# Axis_Channel.net
KiCad netlist of a schematic drawn in Altium Designer
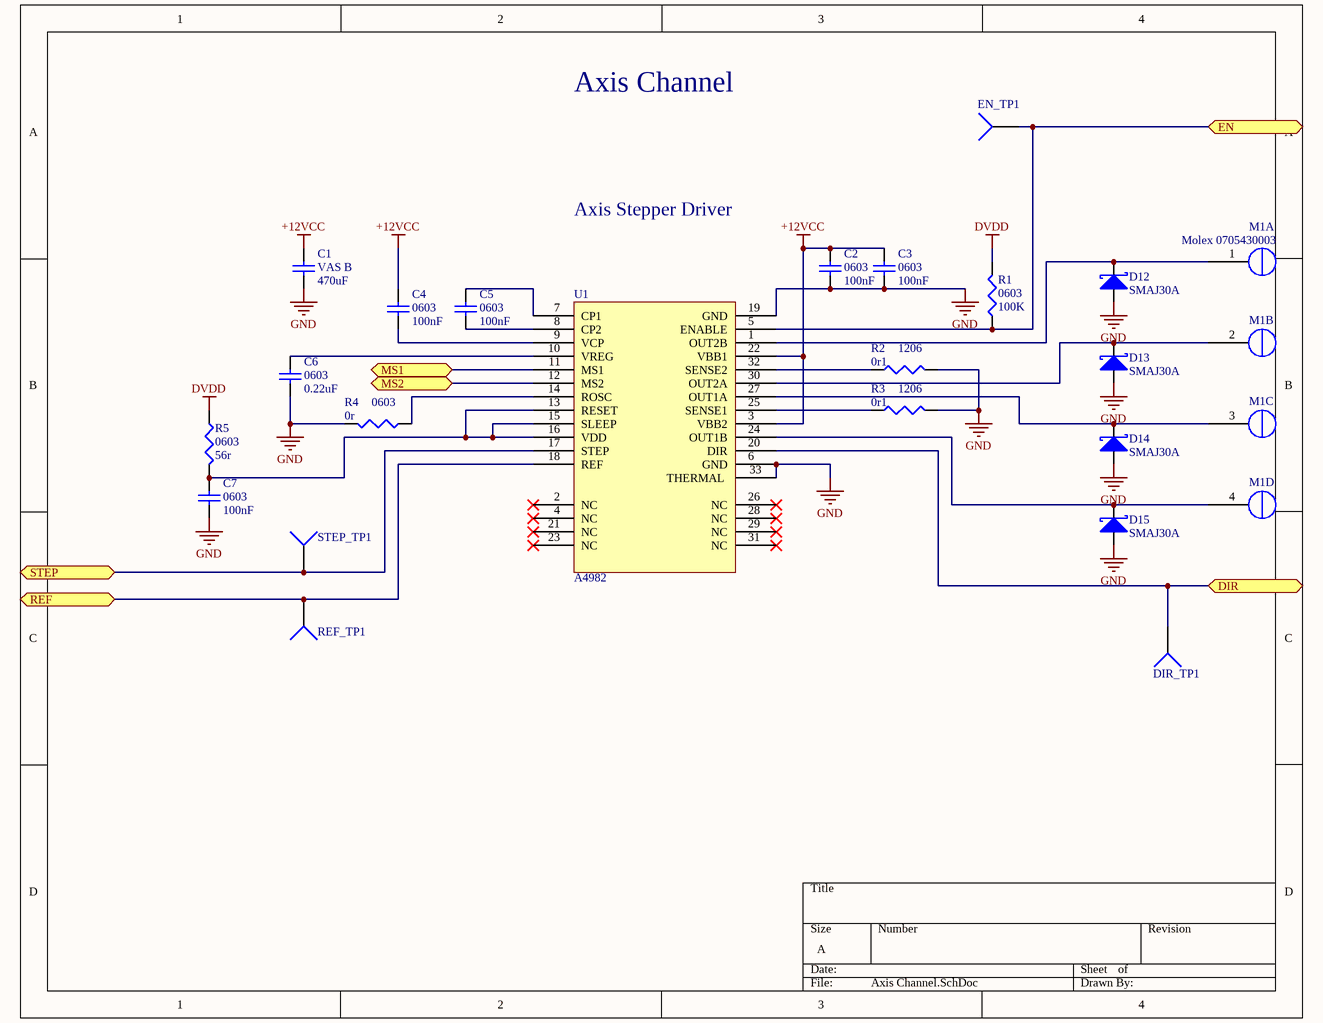
[diagram p0: Axis Channel.SchDoc]

(export (version "E")
  (design (tool "Eeschema 10.0.6"))
  (components
    (comp (ref "C1")
      (value "VAS B")
      (footprint "Panasonic VS B")
      (description "Capacitor (Semiconductor SIM Model)")
      (fields (field (name "ALTIUM_VALUE") "470uF") (field (name "PUBLISHER") "Altium Limited"))
      (libsource (lib "Miscellaneous Devices") (part "Cap Semi"))
    )
    (comp (ref "C2")
      (value "0603")
      (footprint "1608[0603]")
      (description "Capacitor (Semiconductor SIM Model)")
      (fields (field (name "ALTIUM_VALUE") "100nF") (field (name "PUBLISHER") "Altium Limited"))
      (libsource (lib "Miscellaneous Devices") (part "Cap Semi"))
    )
    (comp (ref "C3")
      (value "0603")
      (footprint "1608[0603]")
      (description "Capacitor (Semiconductor SIM Model)")
      (fields (field (name "ALTIUM_VALUE") "100nF") (field (name "PUBLISHER") "Altium Limited"))
      (libsource (lib "Miscellaneous Devices") (part "Cap Semi"))
    )
    (comp (ref "C4")
      (value "0603")
      (footprint "1608[0603]")
      (description "Capacitor (Semiconductor SIM Model)")
      (fields (field (name "ALTIUM_VALUE") "100nF") (field (name "PUBLISHER") "Altium Limited"))
      (libsource (lib "Miscellaneous Devices") (part "Cap Semi"))
    )
    (comp (ref "C5")
      (value "0603")
      (footprint "1608[0603]")
      (description "Capacitor (Semiconductor SIM Model)")
      (fields (field (name "ALTIUM_VALUE") "100nF") (field (name "PUBLISHER") "Altium Limited"))
      (libsource (lib "Miscellaneous Devices") (part "Cap Semi"))
    )
    (comp (ref "C6")
      (value "0603")
      (footprint "1608[0603]")
      (description "Capacitor (Semiconductor SIM Model)")
      (fields (field (name "ALTIUM_VALUE") "0.22uF") (field (name "PUBLISHER") "Altium Limited"))
      (libsource (lib "Miscellaneous Devices") (part "Cap Semi"))
    )
    (comp (ref "C7")
      (value "0603")
      (footprint "1608[0603]")
      (description "Capacitor (Semiconductor SIM Model)")
      (fields (field (name "ALTIUM_VALUE") "100nF") (field (name "PUBLISHER") "Altium Limited"))
      (libsource (lib "Miscellaneous Devices") (part "Cap Semi"))
    )
    (comp (ref "D12")
      (value "SMAJ30A")
      (footprint "SMAJ30A")
      (fields (field (name "PUBLISHER") "Altium Limited"))
      (libsource (lib "ZMBo Schematic Library") (part "D SMAJ30A"))
    )
    (comp (ref "D13")
      (value "SMAJ30A")
      (footprint "SMAJ30A")
      (fields (field (name "PUBLISHER") "Altium Limited"))
      (libsource (lib "ZMBo Schematic Library") (part "D SMAJ30A"))
    )
    (comp (ref "D14")
      (value "SMAJ30A")
      (footprint "SMAJ30A")
      (fields (field (name "PUBLISHER") "Altium Limited"))
      (libsource (lib "ZMBo Schematic Library") (part "D SMAJ30A"))
    )
    (comp (ref "D15")
      (value "SMAJ30A")
      (footprint "SMAJ30A")
      (fields (field (name "PUBLISHER") "Altium Limited"))
      (libsource (lib "ZMBo Schematic Library") (part "D SMAJ30A"))
    )
    (comp (ref "DIR_TP1")
      (value "TP4")
      (footprint "PIN1")
      (description "Socket")
      (fields (field (name "PUBLISHER") "Altium Limited"))
      (libsource (lib "Miscellaneous Connectors") (part "Socket"))
    )
    (comp (ref "EN_TP1")
      (value "TP4")
      (footprint "PIN1")
      (description "Socket")
      (fields (field (name "PUBLISHER") "Altium Limited"))
      (libsource (lib "Miscellaneous Connectors") (part "Socket"))
    )
    (comp (ref "M1")
      (value "Molex 0705430003")
      (footprint "Molex 0705430003")
      (description "Molex 4 Pin Clip Connector")
      (libsource (lib "ZMBo Schematic Library") (part "Molex 0705430003 Alt"))
    )
    (comp (ref "R1")
      (value "0603")
      (footprint "J1-0603")
      (description "Resistor")
      (fields (field (name "ALTIUM_VALUE") "100K") (field (name "PUBLISHER") "Altium Limited"))
      (libsource (lib "Miscellaneous Devices") (part "Res3"))
    )
    (comp (ref "R2")
      (value "1206")
      (footprint "1206 SMD Resistor")
      (description "Resistor")
      (fields (field (name "ALTIUM_VALUE") "0r1") (field (name "PUBLISHER") "Altium Limited"))
      (libsource (lib "Miscellaneous Devices") (part "Res3"))
    )
    (comp (ref "R3")
      (value "1206")
      (footprint "1206 SMD Resistor")
      (description "Resistor")
      (fields (field (name "ALTIUM_VALUE") "0r1") (field (name "PUBLISHER") "Altium Limited"))
      (libsource (lib "Miscellaneous Devices") (part "Res3"))
    )
    (comp (ref "R4")
      (value "0603")
      (footprint "J1-0603")
      (description "Resistor")
      (fields (field (name "ALTIUM_VALUE") "0r") (field (name "PUBLISHER") "Altium Limited"))
      (libsource (lib "Miscellaneous Devices") (part "Res3"))
    )
    (comp (ref "R5")
      (value "0603")
      (footprint "J1-0603")
      (description "Resistor")
      (fields (field (name "ALTIUM_VALUE") "56r") (field (name "PUBLISHER") "Altium Limited"))
      (libsource (lib "Miscellaneous Devices") (part "Res3"))
    )
    (comp (ref "REF_TP1")
      (value "TP4")
      (footprint "PIN1")
      (description "Socket")
      (fields (field (name "PUBLISHER") "Altium Limited"))
      (libsource (lib "Miscellaneous Connectors") (part "Socket"))
    )
    (comp (ref "STEP_TP1")
      (value "TP4")
      (footprint "PIN1")
      (description "Socket")
      (fields (field (name "PUBLISHER") "Altium Limited"))
      (libsource (lib "Miscellaneous Connectors") (part "Socket"))
    )
    (comp (ref "U1")
      (value "A4982")
      (footprint "QFN50P508X508X100_HS-33N")
      (description "Alllegor A4982 Stepper Driver")
      (libsource (lib "RADMBo Schematic Library") (part "A4982"))
    )
  )
  (nets
    (net (code "1") (name "+12VCC") (class "Default")
      (node (ref "C1") (pin "2") (pinfunction "2_2") (pintype "passive"))
      (node (ref "C2") (pin "2") (pinfunction "2_2") (pintype "passive"))
      (node (ref "C3") (pin "2") (pinfunction "2_2") (pintype "passive"))
      (node (ref "C4") (pin "2") (pinfunction "2_2") (pintype "passive"))
      (node (ref "U1") (pin "22") (pinfunction "VBB1_22") (pintype "passive"))
      (node (ref "U1") (pin "3") (pinfunction "VBB2_3") (pintype "passive"))
    )
    (net (code "2") (name "/DIR") (class "Default")
      (node (ref "DIR_TP1") (pin "1") (pinfunction "1_1") (pintype "passive"))
      (node (ref "U1") (pin "20") (pinfunction "DIR_20") (pintype "passive"))
    )
    (net (code "3") (name "/EN") (class "Default")
      (node (ref "EN_TP1") (pin "1") (pinfunction "1_1") (pintype "passive"))
      (node (ref "R1") (pin "1") (pinfunction "1_1") (pintype "passive"))
      (node (ref "U1") (pin "5") (pinfunction "ENABLE_5") (pintype "passive"))
    )
    (net (code "4") (name "/MS1") (class "Default")
      (node (ref "U1") (pin "11") (pinfunction "MS1_11") (pintype "passive"))
    )
    (net (code "5") (name "/MS2") (class "Default")
      (node (ref "U1") (pin "12") (pinfunction "MS2_12") (pintype "passive"))
    )
    (net (code "6") (name "/REF") (class "Default")
      (node (ref "REF_TP1") (pin "1") (pinfunction "1_1") (pintype "passive"))
      (node (ref "U1") (pin "18") (pinfunction "REF_18") (pintype "passive"))
    )
    (net (code "7") (name "/STEP") (class "Default")
      (node (ref "STEP_TP1") (pin "1") (pinfunction "1_1") (pintype "passive"))
      (node (ref "U1") (pin "17") (pinfunction "STEP_17") (pintype "passive"))
    )
    (net (code "8") (name "DVDD") (class "Default")
      (node (ref "R1") (pin "2") (pinfunction "2_2") (pintype "passive"))
      (node (ref "R5") (pin "1") (pinfunction "1_1") (pintype "passive"))
    )
    (net (code "9") (name "GND") (class "Default")
      (node (ref "C1") (pin "1") (pinfunction "1_1") (pintype "passive"))
      (node (ref "C2") (pin "1") (pinfunction "1_1") (pintype "passive"))
      (node (ref "C3") (pin "1") (pinfunction "1_1") (pintype "passive"))
      (node (ref "C6") (pin "1") (pinfunction "1_1") (pintype "passive"))
      (node (ref "C7") (pin "1") (pinfunction "1_1") (pintype "passive"))
      (node (ref "D12") (pin "1") (pinfunction "A_1") (pintype "passive"))
      (node (ref "D13") (pin "1") (pinfunction "A_1") (pintype "passive"))
      (node (ref "D14") (pin "1") (pinfunction "A_1") (pintype "passive"))
      (node (ref "D15") (pin "1") (pinfunction "A_1") (pintype "passive"))
      (node (ref "R2") (pin "2") (pinfunction "2_2") (pintype "passive"))
      (node (ref "R3") (pin "2") (pinfunction "2_2") (pintype "passive"))
      (node (ref "R4") (pin "2") (pinfunction "2_2") (pintype "passive"))
      (node (ref "U1") (pin "19") (pinfunction "GND_19") (pintype "passive"))
      (node (ref "U1") (pin "33") (pinfunction "THERMAL_33") (pintype "passive"))
      (node (ref "U1") (pin "6") (pinfunction "GND_6") (pintype "passive"))
    )
    (net (code "10") (name "Net-(D12-K)") (class "Default")
      (node (ref "D12") (pin "2") (pinfunction "K_2") (pintype "passive"))
      (node (ref "M1") (pin "1") (pinfunction "OUT2B_1") (pintype "passive"))
      (node (ref "U1") (pin "1") (pinfunction "OUT2B_1") (pintype "passive"))
    )
    (net (code "11") (name "Net-(D13-K)") (class "Default")
      (node (ref "D13") (pin "2") (pinfunction "K_2") (pintype "passive"))
      (node (ref "M1") (pin "2") (pinfunction "OUT2A_2") (pintype "passive"))
      (node (ref "U1") (pin "30") (pinfunction "OUT2A_30") (pintype "passive"))
    )
    (net (code "12") (name "Net-(D14-K)") (class "Default")
      (node (ref "D14") (pin "2") (pinfunction "K_2") (pintype "passive"))
      (node (ref "M1") (pin "3") (pinfunction "OUT1A_3") (pintype "passive"))
      (node (ref "U1") (pin "27") (pinfunction "OUT1A_27") (pintype "passive"))
    )
    (net (code "13") (name "Net-(D15-K)") (class "Default")
      (node (ref "D15") (pin "2") (pinfunction "K_2") (pintype "passive"))
      (node (ref "M1") (pin "4") (pinfunction "OUT1B_4") (pintype "passive"))
      (node (ref "U1") (pin "24") (pinfunction "OUT1B_24") (pintype "passive"))
    )
    (net (code "14") (name "Net-(U1-CP1)") (class "Default")
      (node (ref "C5") (pin "2") (pinfunction "2_2") (pintype "passive"))
      (node (ref "U1") (pin "7") (pinfunction "CP1_7") (pintype "passive"))
    )
    (net (code "15") (name "Net-(U1-CP2)") (class "Default")
      (node (ref "C5") (pin "1") (pinfunction "1_1") (pintype "passive"))
      (node (ref "U1") (pin "8") (pinfunction "CP2_8") (pintype "passive"))
    )
    (net (code "16") (name "Net-(U1-RESET)") (class "Default")
      (node (ref "C7") (pin "2") (pinfunction "2_2") (pintype "passive"))
      (node (ref "R5") (pin "2") (pinfunction "2_2") (pintype "passive"))
      (node (ref "U1") (pin "13") (pinfunction "RESET_13") (pintype "passive"))
      (node (ref "U1") (pin "15") (pinfunction "SLEEP_15") (pintype "passive"))
      (node (ref "U1") (pin "16") (pinfunction "VDD_16") (pintype "passive"))
    )
    (net (code "17") (name "Net-(U1-ROSC)") (class "Default")
      (node (ref "R4") (pin "1") (pinfunction "1_1") (pintype "passive"))
      (node (ref "U1") (pin "14") (pinfunction "ROSC_14") (pintype "passive"))
    )
    (net (code "18") (name "Net-(U1-SENSE1)") (class "Default")
      (node (ref "R3") (pin "1") (pinfunction "1_1") (pintype "passive"))
      (node (ref "U1") (pin "25") (pinfunction "SENSE1_25") (pintype "passive"))
    )
    (net (code "19") (name "Net-(U1-SENSE2)") (class "Default")
      (node (ref "R2") (pin "1") (pinfunction "1_1") (pintype "passive"))
      (node (ref "U1") (pin "32") (pinfunction "SENSE2_32") (pintype "passive"))
    )
    (net (code "20") (name "Net-(U1-VCP)") (class "Default")
      (node (ref "C4") (pin "1") (pinfunction "1_1") (pintype "passive"))
      (node (ref "U1") (pin "9") (pinfunction "VCP_9") (pintype "passive"))
    )
    (net (code "21") (name "Net-(U1-VREG)") (class "Default")
      (node (ref "C6") (pin "2") (pinfunction "2_2") (pintype "passive"))
      (node (ref "U1") (pin "10") (pinfunction "VREG_10") (pintype "passive"))
    )
    (net (code "22") (name "unconnected-(U1-NC-Pad2)") (class "Default")
      (node (ref "U1") (pin "2") (pinfunction "NC_2") (pintype "passive+no_connect"))
    )
    (net (code "23") (name "unconnected-(U1-NC-Pad4)") (class "Default")
      (node (ref "U1") (pin "4") (pinfunction "NC_4") (pintype "passive+no_connect"))
    )
    (net (code "24") (name "unconnected-(U1-NC-Pad21)") (class "Default")
      (node (ref "U1") (pin "21") (pinfunction "NC_21") (pintype "passive+no_connect"))
    )
    (net (code "25") (name "unconnected-(U1-NC-Pad23)") (class "Default")
      (node (ref "U1") (pin "23") (pinfunction "NC_23") (pintype "passive+no_connect"))
    )
    (net (code "26") (name "unconnected-(U1-NC-Pad26)") (class "Default")
      (node (ref "U1") (pin "26") (pinfunction "NC_26") (pintype "passive+no_connect"))
    )
    (net (code "27") (name "unconnected-(U1-NC-Pad28)") (class "Default")
      (node (ref "U1") (pin "28") (pinfunction "NC_28") (pintype "passive+no_connect"))
    )
    (net (code "28") (name "unconnected-(U1-NC-Pad29)") (class "Default")
      (node (ref "U1") (pin "29") (pinfunction "NC_29") (pintype "passive+no_connect"))
    )
    (net (code "29") (name "unconnected-(U1-NC-Pad31)") (class "Default")
      (node (ref "U1") (pin "31") (pinfunction "NC_31") (pintype "passive+no_connect"))
    )
  )
)
